# us__1sch.net
KiCad netlist of a schematic drawn in Altium Designer
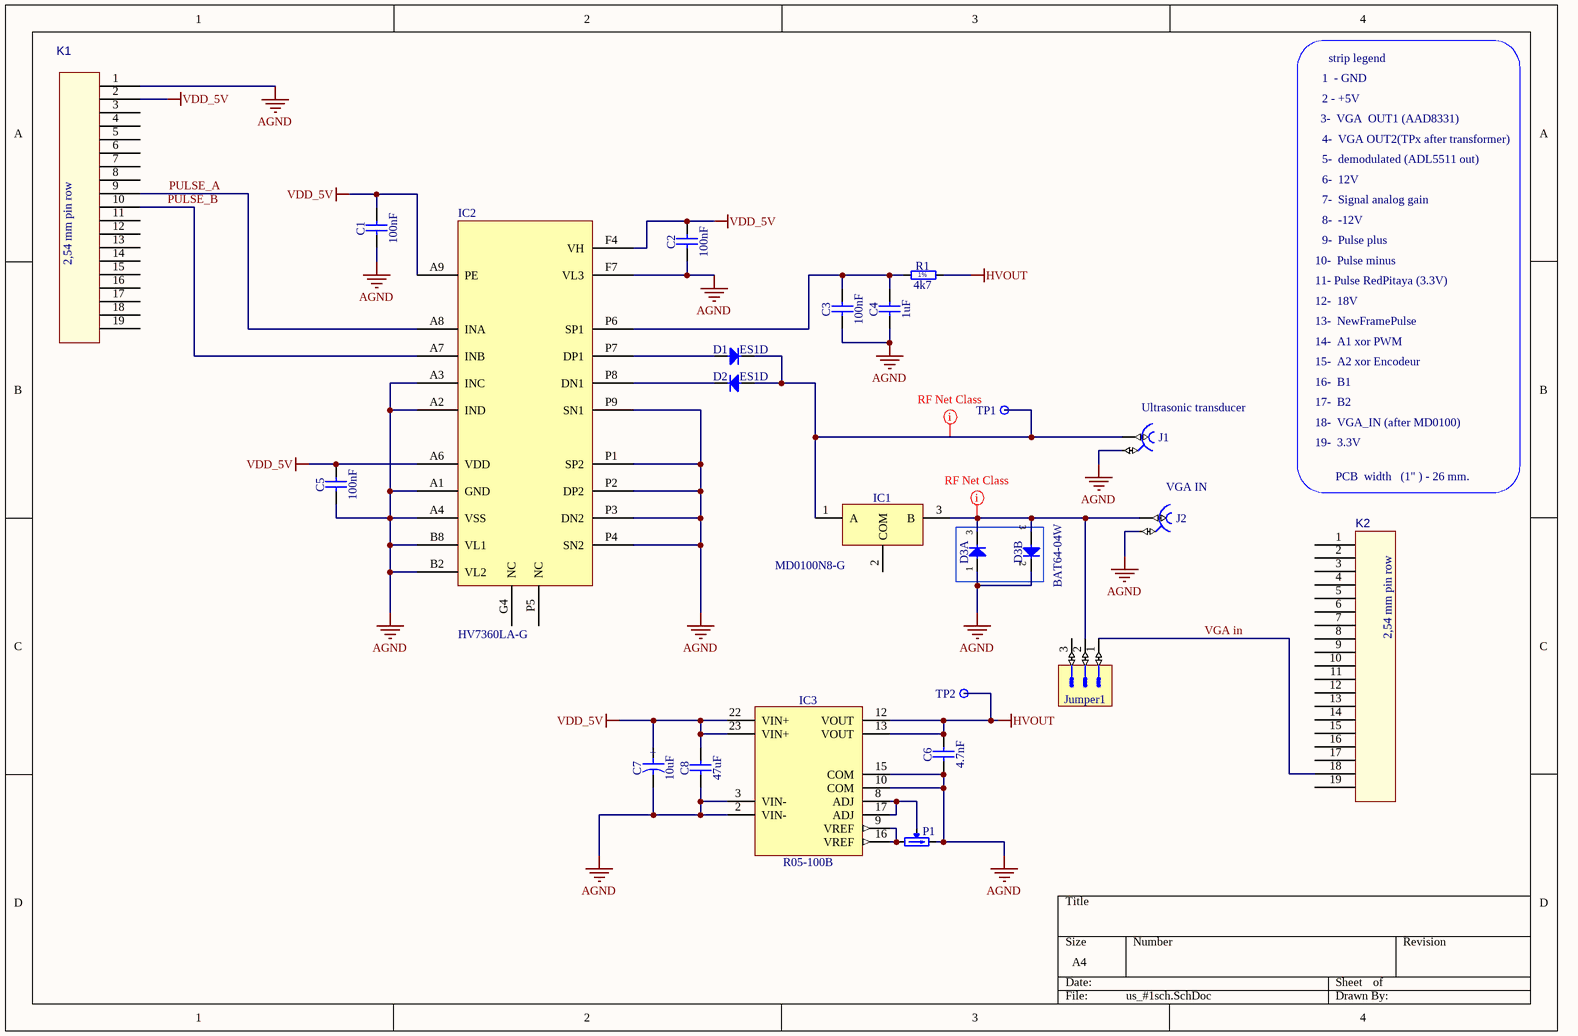
[diagram p0: us_#1sch.SchDoc]

(export (version "E")
  (design (tool "Eeschema 10.0.6"))
  (components
    (comp (ref "C1")
      (value "100nF")
      (footprint "echOpen_ADC_Card:CAPC1608X87N")
      (description "Non-polarised capacitor")
      (fields
        (field (name "PART NUMBER") "CC0603_100NF_50V_10%_X7R")
        (field (name "VOLTAGE") "50V")
        (field (name "AUTHOR") "CERN DEM JLC")
      )
      (libsource (lib "Sof-Capacitors") (part "Capacitor - non polarized"))
    )
    (comp (ref "C2")
      (value "100nF")
      (footprint "echOpen_ADC_Card:CAPC1608X87N")
      (description "Non-polarised capacitor")
      (fields
        (field (name "PART NUMBER") "CC0603_100NF_50V_10%_X7R")
        (field (name "VOLTAGE") "50V")
        (field (name "AUTHOR") "CERN DEM JLC")
      )
      (libsource (lib "Sof-Capacitors") (part "Capacitor - non polarized"))
    )
    (comp (ref "C3")
      (value "100nF")
      (footprint "echOpen_ADC_Card:CAPC1608X87N")
      (description "Non-polarised capacitor")
      (fields
        (field (name "PART NUMBER") "CC0603_100NF_50V_10%_X7R")
        (field (name "VOLTAGE") "50V")
        (field (name "AUTHOR") "CERN DEM JLC")
      )
      (libsource (lib "Sof-Capacitors") (part "Capacitor - non polarized"))
    )
    (comp (ref "C4")
      (value "1uF")
      (footprint "echOpen_ADC_Card:CAPC5650X165N")
      (description "Non-polarised capacitor")
      (fields
        (field (name "PART NUMBER") "CC2220_1UF_200V_10%_X7R")
        (field (name "VOLTAGE") "200V")
        (field (name "AUTHOR") "CERN DEM JLC")
      )
      (libsource (lib "Sof-Capacitors") (part "Capacitor - non polarized"))
    )
    (comp (ref "C5")
      (value "100nF")
      (footprint "echOpen_ADC_Card:CAPC1608X87N")
      (description "Non-polarised capacitor")
      (fields
        (field (name "PART NUMBER") "CC0603_100NF_50V_10%_X7R")
        (field (name "VOLTAGE") "50V")
        (field (name "AUTHOR") "CERN DEM JLC")
      )
      (libsource (lib "Sof-Capacitors") (part "Capacitor - non polarized"))
    )
    (comp (ref "C6")
      (value "4.7nF")
      (footprint "echOpen_ADC_Card:CAPC2012X110N")
      (description "Non-polarised capacitor")
      (fields
        (field (name "PART NUMBER") "CC0805_4.7NF_250V_10%_X7R")
        (field (name "VOLTAGE") "250V")
        (field (name "AUTHOR") "S. Jafar")
      )
      (libsource (lib "Sof-Capacitors") (part "Capacitor - non polarized"))
    )
    (comp (ref "C7")
      (value "10uF")
      (footprint "echOpen_ADC_Card:CAPMP3528X210N")
      (description "Polarised capacitor")
      (fields
        (field (name "PART NUMBER") "CTE3528-21_10UF_16V_10%_LESR0800")
        (field (name "VOLTAGE") "16V")
        (field (name "AUTHOR") "CERN DEM JLC")
      )
      (libsource (lib "Sof-Capacitors") (part "Capacitor - polarized"))
    )
    (comp (ref "C8")
      (value "47uF")
      (footprint "echOpen_ADC_Card:CAPC3216X180N")
      (description "Non-polarised capacitor")
      (fields
        (field (name "PART NUMBER") "CC1206_47UF_25V_20%_X5R")
        (field (name "VOLTAGE") "25V")
        (field (name "AUTHOR") "CERN DEM JLC")
      )
      (libsource (lib "Sof-Capacitors") (part "Capacitor - non polarized"))
    )
    (comp (ref "D1")
      (value "ES1D")
      (footprint "echOpen_ADC_Card:DIOM5027X244N")
      (description "Diode")
      (fields
        (field (name "VOLTAGE") "200V")
        (field (name "POWER") "1A")
        (field (name "AUTHOR") "CERN DEM JLC")
      )
      (libsource (lib "Sof-ICs And Semiconductors") (part "Diode"))
    )
    (comp (ref "D2")
      (value "ES1D")
      (footprint "echOpen_ADC_Card:DIOM5027X244N")
      (description "Diode")
      (fields
        (field (name "VOLTAGE") "200V")
        (field (name "POWER") "1A")
        (field (name "AUTHOR") "CERN DEM JLC")
      )
      (libsource (lib "Sof-ICs And Semiconductors") (part "Diode"))
    )
    (comp (ref "D3")
      (value "BAT64-04W")
      (footprint "echOpen_ADC_Card:SOT65P210X100-3N")
      (description "Serial Diode")
      (fields
        (field (name "VOLTAGE") "40V")
        (field (name "POWER") "250mW")
        (field (name "AUTHOR") "CERN DEM JMW")
      )
      (libsource (lib "Sof-ICs And Semiconductors") (part "Diode x2 A1C3_A3C2"))
    )
    (comp (ref "IC1")
      (value "MD0100N8-G")
      (footprint "echOpen_ADC_Card:SOT89")
      (description "3-Ultra-Sound HV Switch 1=A 2=COM 3=B")
      (fields (field (name "MANUFACTURER") "Supertex inc.") (field (name "AUTHOR") "S. Jafar"))
      (libsource (lib "Sof-ICs And Semiconductors") (part "MD0100"))
    )
    (comp (ref "IC2")
      (value "HV7360LA-G")
      (footprint "HV7360_BGA")
      (fields (field (name "MANUFACTURER") "Supertex inc.") (field (name "AUTHOR") "S. Jafar"))
      (libsource (lib "Schlib2") (part "HV7360_BGA"))
    )
    (comp (ref "IC3")
      (value "R05-100B")
      (footprint "echOpen_ADC_Card:PWS_RECOM_R05-100B")
      (description "Power Supply")
      (fields (field (name "MANUFACTURER") "RECOM POWER") (field (name "AUTHOR") "S. Jafar"))
      (libsource (lib "echOpen_ADC_Card") (part "PWS_RECOM_R05-100B"))
    )
    (comp (ref "J1")
      (value "SMA")
      (footprint "echOpen_ADC_Card:AMPHENOL_132357-11")
      (fields
        (field (name "PART NUMBER") "AMPHENOL_132357-11")
        (field (name "MANUFACTURER") "AMPHENOL")
        (field (name "MANUFACTURER PART NUMBER") "132357-11")
        (field (name "AUTHOR") "CERN DEM JLC")
      )
      (libsource (lib "Sof-Connectors") (part "Coax_1Female_1Shield"))
    )
    (comp (ref "J2")
      (value "SMA")
      (footprint "echOpen_ADC_Card:AMPHENOL_132357-11")
      (fields
        (field (name "PART NUMBER") "AMPHENOL_132357-11")
        (field (name "MANUFACTURER") "AMPHENOL")
        (field (name "MANUFACTURER PART NUMBER") "132357-11")
        (field (name "AUTHOR") "CERN DEM JLC")
      )
      (libsource (lib "Sof-Connectors") (part "Coax_1Female_1Shield"))
    )
    (comp (ref "Jumper1")
      (value "~")
      (footprint "echOpen_ADC_Card:SULLINS_GRPB031VWVN")
      (description "Connector 3 Male")
      (fields
        (field (name "PART NUMBER") "SULLINS_GRPB031VWVN")
        (field (name "MANUFACTURER") "SULLINS")
        (field (name "AUTHOR") "S. Jafar")
      )
      (libsource (lib "echOpen_ADC_Card") (part "Connector 3 Male"))
    )
    (comp (ref "K1")
      (value "PLS_2.54mm-19")
      (footprint "PLS_2.54mm-19")
      (libsource (lib "") (part "PLS_2.54mm-19_1"))
    )
    (comp (ref "K2")
      (value "PLS_2.54mm-19")
      (footprint "PLS_2.54mm-19")
      (libsource (lib "alt_vovan") (part "PLS_2.54mm-19"))
    )
    (comp (ref "P1")
      (value "5k")
      (footprint "echOpen_ADC_Card:TRIM_BOURNS_3223W")
      (description "Trimming Potentiometer")
      (fields
        (field (name "PART NUMBER") "TRIM_11T_5K_BOURNS_3223W-1-502E")
        (field (name "POWER") "0.125W")
        (field (name "AUTHOR") "CERN DEM JLC")
      )
      (libsource (lib "Sof-Resistors") (part "Trimming Potentiometer"))
    )
    (comp (ref "R1")
      (value "4k7")
      (footprint "echOpen_ADC_Card:RESC3216X65N")
      (description "Resistor - 1%")
      (fields
        (field (name "PART NUMBER") "R1206_4K7_1%_0.25W_100PPM")
        (field (name "POWER") "0.25W")
        (field (name "AUTHOR") "CERN DEM JLC")
      )
      (libsource (lib "Sof-Resistors") (part "Resistor - 1%"))
    )
    (comp (ref "TP1")
      (value "Test Point")
      (footprint "echOpen_ADC_Card:NICOMATIC_C12000B")
      (fields
        (field (name "PART NUMBER") "NICOMATIC_C12000B")
        (field (name "MANUFACTURER") "NICOMATIC")
        (field (name "MANUFACTURER PART NUMBER") "C12000B")
        (field (name "AUTHOR") "CERN DEM JLC")
      )
      (libsource (lib "Sof-Connectors") (part "Test Point"))
    )
    (comp (ref "TP2")
      (value "Test Point")
      (footprint "echOpen_ADC_Card:NICOMATIC_C12000B")
      (fields
        (field (name "PART NUMBER") "NICOMATIC_C12000B")
        (field (name "MANUFACTURER") "NICOMATIC")
        (field (name "MANUFACTURER PART NUMBER") "C12000B")
        (field (name "AUTHOR") "CERN DEM JLC")
      )
      (libsource (lib "Sof-Connectors") (part "Test Point"))
    )
  )
  (nets
    (net (code "1") (name "/PULSE_A") (class "Default")
      (node (ref "IC2") (pin "A8") (pinfunction "INA_A8") (pintype "passive"))
      (node (ref "K1") (pin "9") (pinfunction "9_9") (pintype "passive"))
    )
    (net (code "2") (name "/PULSE_B") (class "Default")
      (node (ref "IC2") (pin "A7") (pinfunction "INB_A7") (pintype "passive"))
      (node (ref "K1") (pin "10") (pinfunction "10_10") (pintype "passive"))
    )
    (net (code "3") (name "/VGA in") (class "Default")
      (node (ref "Jumper1") (pin "1") (pinfunction "1_1") (pintype "bidirectional"))
      (node (ref "K2") (pin "18") (pinfunction "18_18") (pintype "passive"))
    )
    (net (code "4") (name "AGND") (class "Default")
      (node (ref "C1") (pin "1") (pinfunction "1_1") (pintype "passive"))
      (node (ref "C2") (pin "1") (pinfunction "1_1") (pintype "passive"))
      (node (ref "C3") (pin "1") (pinfunction "1_1") (pintype "passive"))
      (node (ref "C4") (pin "1") (pinfunction "1_1") (pintype "passive"))
      (node (ref "C5") (pin "1") (pinfunction "1_1") (pintype "passive"))
      (node (ref "C6") (pin "1") (pinfunction "1_1") (pintype "passive"))
      (node (ref "C7") (pin "2") (pinfunction "2_2") (pintype "passive"))
      (node (ref "C8") (pin "1") (pinfunction "1_1") (pintype "passive"))
      (node (ref "D3") (pin "1") (pinfunction "A_1") (pintype "passive"))
      (node (ref "D3") (pin "2") (pinfunction "C_2") (pintype "passive"))
      (node (ref "IC2") (pin "A1") (pinfunction "GND_A1") (pintype "passive"))
      (node (ref "IC2") (pin "A2") (pinfunction "IND_A2") (pintype "passive"))
      (node (ref "IC2") (pin "A3") (pinfunction "INC_A3") (pintype "passive"))
      (node (ref "IC2") (pin "A4") (pinfunction "VSS_A4") (pintype "passive"))
      (node (ref "IC2") (pin "B2") (pinfunction "VL2_B2") (pintype "passive"))
      (node (ref "IC2") (pin "B8") (pinfunction "VL1_B8") (pintype "passive"))
      (node (ref "IC2") (pin "F7") (pinfunction "VL3_F7") (pintype "passive"))
      (node (ref "IC2") (pin "P1") (pinfunction "SP2_P1") (pintype "passive"))
      (node (ref "IC2") (pin "P2") (pinfunction "DP2_P2") (pintype "passive"))
      (node (ref "IC2") (pin "P3") (pinfunction "DN2_P3") (pintype "passive"))
      (node (ref "IC2") (pin "P4") (pinfunction "SN2_P4") (pintype "passive"))
      (node (ref "IC2") (pin "P9") (pinfunction "SN1_P9") (pintype "passive"))
      (node (ref "IC3") (pin "10") (pinfunction "COM_10") (pintype "power_in"))
      (node (ref "IC3") (pin "15") (pinfunction "COM_15") (pintype "power_in"))
      (node (ref "IC3") (pin "2") (pinfunction "VIN-_2") (pintype "passive"))
      (node (ref "IC3") (pin "3") (pinfunction "VIN-_3") (pintype "passive"))
      (node (ref "J1") (pin "2") (pinfunction "2_2") (pintype "bidirectional"))
      (node (ref "J2") (pin "2") (pinfunction "2_2") (pintype "bidirectional"))
      (node (ref "K1") (pin "1") (pinfunction "1_1") (pintype "passive"))
      (node (ref "P1") (pin "3") (pinfunction "CW_3") (pintype "passive"))
    )
    (net (code "5") (name "HVOUT") (class "Default")
      (node (ref "C6") (pin "2") (pinfunction "2_2") (pintype "passive"))
      (node (ref "IC3") (pin "12") (pinfunction "VOUT_12") (pintype "power_in"))
      (node (ref "IC3") (pin "13") (pinfunction "VOUT_13") (pintype "power_in"))
      (node (ref "R1") (pin "2") (pinfunction "2_2") (pintype "passive"))
      (node (ref "TP2") (pin "1") (pinfunction "1_1") (pintype "bidirectional"))
    )
    (net (code "6") (name "Net-(D1-A)") (class "Default")
      (node (ref "D1") (pin "2") (pinfunction "A_2") (pintype "passive"))
      (node (ref "IC2") (pin "P7") (pinfunction "DP1_P7") (pintype "passive"))
    )
    (net (code "7") (name "Net-(D1-C)") (class "Default")
      (node (ref "D1") (pin "1") (pinfunction "C_1") (pintype "passive"))
      (node (ref "D2") (pin "2") (pinfunction "A_2") (pintype "passive"))
      (node (ref "IC1") (pin "1") (pinfunction "A_1") (pintype "passive"))
      (node (ref "J1") (pin "1") (pinfunction "1_1") (pintype "bidirectional"))
      (node (ref "TP1") (pin "1") (pinfunction "1_1") (pintype "bidirectional"))
    )
    (net (code "8") (name "Net-(D2-C)") (class "Default")
      (node (ref "D2") (pin "1") (pinfunction "C_1") (pintype "passive"))
      (node (ref "IC2") (pin "P8") (pinfunction "DN1_P8") (pintype "passive"))
    )
    (net (code "9") (name "Net-(D3A-COMAC)") (class "Default")
      (node (ref "D3") (pin "3") (pinfunction "COMAC_3") (pintype "passive"))
      (node (ref "IC1") (pin "3") (pinfunction "B_3") (pintype "passive"))
      (node (ref "J2") (pin "1") (pinfunction "1_1") (pintype "bidirectional"))
      (node (ref "Jumper1") (pin "2") (pinfunction "2_2") (pintype "bidirectional"))
    )
    (net (code "10") (name "Net-(IC2-SP1)") (class "Default")
      (node (ref "C3") (pin "2") (pinfunction "2_2") (pintype "passive"))
      (node (ref "C4") (pin "2") (pinfunction "2_2") (pintype "passive"))
      (node (ref "IC2") (pin "P6") (pinfunction "SP1_P6") (pintype "passive"))
      (node (ref "R1") (pin "1") (pinfunction "1_1") (pintype "passive"))
    )
    (net (code "11") (name "Net-(P1-CCW)") (class "Default")
      (node (ref "IC3") (pin "16") (pinfunction "VREF_16") (pintype "output"))
      (node (ref "IC3") (pin "9") (pinfunction "VREF_9") (pintype "output"))
      (node (ref "P1") (pin "1") (pinfunction "CCW_1") (pintype "passive"))
    )
    (net (code "12") (name "Net-(P1-W)") (class "Default")
      (node (ref "IC3") (pin "17") (pinfunction "ADJ_17") (pintype "passive"))
      (node (ref "IC3") (pin "8") (pinfunction "ADJ_8") (pintype "passive"))
      (node (ref "P1") (pin "2") (pinfunction "W_2") (pintype "passive"))
    )
    (net (code "13") (name "VDD_5V") (class "Default")
      (node (ref "C1") (pin "2") (pinfunction "2_2") (pintype "passive"))
      (node (ref "C2") (pin "2") (pinfunction "2_2") (pintype "passive"))
      (node (ref "C5") (pin "2") (pinfunction "2_2") (pintype "passive"))
      (node (ref "C7") (pin "1") (pinfunction "1_1") (pintype "passive"))
      (node (ref "C8") (pin "2") (pinfunction "2_2") (pintype "passive"))
      (node (ref "IC2") (pin "A6") (pinfunction "VDD_A6") (pintype "passive"))
      (node (ref "IC2") (pin "A9") (pinfunction "PE_A9") (pintype "passive"))
      (node (ref "IC2") (pin "F4") (pinfunction "VH_F4") (pintype "passive"))
      (node (ref "IC3") (pin "22") (pinfunction "VIN+_22") (pintype "power_in"))
      (node (ref "IC3") (pin "23") (pinfunction "VIN+_23") (pintype "power_in"))
      (node (ref "K1") (pin "2") (pinfunction "2_2") (pintype "passive"))
    )
    (net (code "14") (name "unconnected-(IC1-COM-Pad2)") (class "Default")
      (node (ref "IC1") (pin "2") (pinfunction "COM_2") (pintype "passive"))
    )
    (net (code "15") (name "unconnected-(IC2-NC-PadG4)") (class "Default")
      (node (ref "IC2") (pin "G4") (pinfunction "NC_G4") (pintype "passive"))
    )
    (net (code "16") (name "unconnected-(IC2-NC-PadP5)") (class "Default")
      (node (ref "IC2") (pin "P5") (pinfunction "NC_P5") (pintype "passive"))
    )
    (net (code "17") (name "unconnected-(Jumper1-Pad3)") (class "Default")
      (node (ref "Jumper1") (pin "3") (pinfunction "3_3") (pintype "bidirectional"))
    )
    (net (code "18") (name "unconnected-(K1-Pad3)") (class "Default")
      (node (ref "K1") (pin "3") (pinfunction "3_3") (pintype "passive"))
    )
    (net (code "19") (name "unconnected-(K1-Pad4)") (class "Default")
      (node (ref "K1") (pin "4") (pinfunction "4_4") (pintype "passive"))
    )
    (net (code "20") (name "unconnected-(K1-Pad5)") (class "Default")
      (node (ref "K1") (pin "5") (pinfunction "5_5") (pintype "passive"))
    )
    (net (code "21") (name "unconnected-(K1-Pad6)") (class "Default")
      (node (ref "K1") (pin "6") (pinfunction "6_6") (pintype "passive"))
    )
    (net (code "22") (name "unconnected-(K1-Pad7)") (class "Default")
      (node (ref "K1") (pin "7") (pinfunction "7_7") (pintype "passive"))
    )
    (net (code "23") (name "unconnected-(K1-Pad8)") (class "Default")
      (node (ref "K1") (pin "8") (pinfunction "8_8") (pintype "passive"))
    )
    (net (code "24") (name "unconnected-(K1-Pad11)") (class "Default")
      (node (ref "K1") (pin "11") (pinfunction "11_11") (pintype "passive"))
    )
    (net (code "25") (name "unconnected-(K1-Pad12)") (class "Default")
      (node (ref "K1") (pin "12") (pinfunction "12_12") (pintype "passive"))
    )
    (net (code "26") (name "unconnected-(K1-Pad13)") (class "Default")
      (node (ref "K1") (pin "13") (pinfunction "13_13") (pintype "passive"))
    )
    (net (code "27") (name "unconnected-(K1-Pad14)") (class "Default")
      (node (ref "K1") (pin "14") (pinfunction "14_14") (pintype "passive"))
    )
    (net (code "28") (name "unconnected-(K1-Pad15)") (class "Default")
      (node (ref "K1") (pin "15") (pinfunction "15_15") (pintype "passive"))
    )
    (net (code "29") (name "unconnected-(K1-Pad16)") (class "Default")
      (node (ref "K1") (pin "16") (pinfunction "16_16") (pintype "passive"))
    )
    (net (code "30") (name "unconnected-(K1-Pad17)") (class "Default")
      (node (ref "K1") (pin "17") (pinfunction "17_17") (pintype "passive"))
    )
    (net (code "31") (name "unconnected-(K1-Pad18)") (class "Default")
      (node (ref "K1") (pin "18") (pinfunction "18_18") (pintype "passive"))
    )
    (net (code "32") (name "unconnected-(K1-Pad19)") (class "Default")
      (node (ref "K1") (pin "19") (pinfunction "19_19") (pintype "passive"))
    )
    (net (code "33") (name "unconnected-(K2-Pad1)") (class "Default")
      (node (ref "K2") (pin "1") (pinfunction "1_1") (pintype "passive"))
    )
    (net (code "34") (name "unconnected-(K2-Pad2)") (class "Default")
      (node (ref "K2") (pin "2") (pinfunction "2_2") (pintype "passive"))
    )
    (net (code "35") (name "unconnected-(K2-Pad3)") (class "Default")
      (node (ref "K2") (pin "3") (pinfunction "3_3") (pintype "passive"))
    )
    (net (code "36") (name "unconnected-(K2-Pad4)") (class "Default")
      (node (ref "K2") (pin "4") (pinfunction "4_4") (pintype "passive"))
    )
    (net (code "37") (name "unconnected-(K2-Pad5)") (class "Default")
      (node (ref "K2") (pin "5") (pinfunction "5_5") (pintype "passive"))
    )
    (net (code "38") (name "unconnected-(K2-Pad6)") (class "Default")
      (node (ref "K2") (pin "6") (pinfunction "6_6") (pintype "passive"))
    )
    (net (code "39") (name "unconnected-(K2-Pad7)") (class "Default")
      (node (ref "K2") (pin "7") (pinfunction "7_7") (pintype "passive"))
    )
    (net (code "40") (name "unconnected-(K2-Pad8)") (class "Default")
      (node (ref "K2") (pin "8") (pinfunction "8_8") (pintype "passive"))
    )
    (net (code "41") (name "unconnected-(K2-Pad9)") (class "Default")
      (node (ref "K2") (pin "9") (pinfunction "9_9") (pintype "passive"))
    )
    (net (code "42") (name "unconnected-(K2-Pad10)") (class "Default")
      (node (ref "K2") (pin "10") (pinfunction "10_10") (pintype "passive"))
    )
    (net (code "43") (name "unconnected-(K2-Pad11)") (class "Default")
      (node (ref "K2") (pin "11") (pinfunction "11_11") (pintype "passive"))
    )
    (net (code "44") (name "unconnected-(K2-Pad12)") (class "Default")
      (node (ref "K2") (pin "12") (pinfunction "12_12") (pintype "passive"))
    )
    (net (code "45") (name "unconnected-(K2-Pad13)") (class "Default")
      (node (ref "K2") (pin "13") (pinfunction "13_13") (pintype "passive"))
    )
    (net (code "46") (name "unconnected-(K2-Pad14)") (class "Default")
      (node (ref "K2") (pin "14") (pinfunction "14_14") (pintype "passive"))
    )
    (net (code "47") (name "unconnected-(K2-Pad15)") (class "Default")
      (node (ref "K2") (pin "15") (pinfunction "15_15") (pintype "passive"))
    )
    (net (code "48") (name "unconnected-(K2-Pad16)") (class "Default")
      (node (ref "K2") (pin "16") (pinfunction "16_16") (pintype "passive"))
    )
    (net (code "49") (name "unconnected-(K2-Pad17)") (class "Default")
      (node (ref "K2") (pin "17") (pinfunction "17_17") (pintype "passive"))
    )
    (net (code "50") (name "unconnected-(K2-Pad19)") (class "Default")
      (node (ref "K2") (pin "19") (pinfunction "19_19") (pintype "passive"))
    )
  )
)
